# WS2811_Extender_V1_1.net
KiCad netlist of a schematic drawn in EAGLE
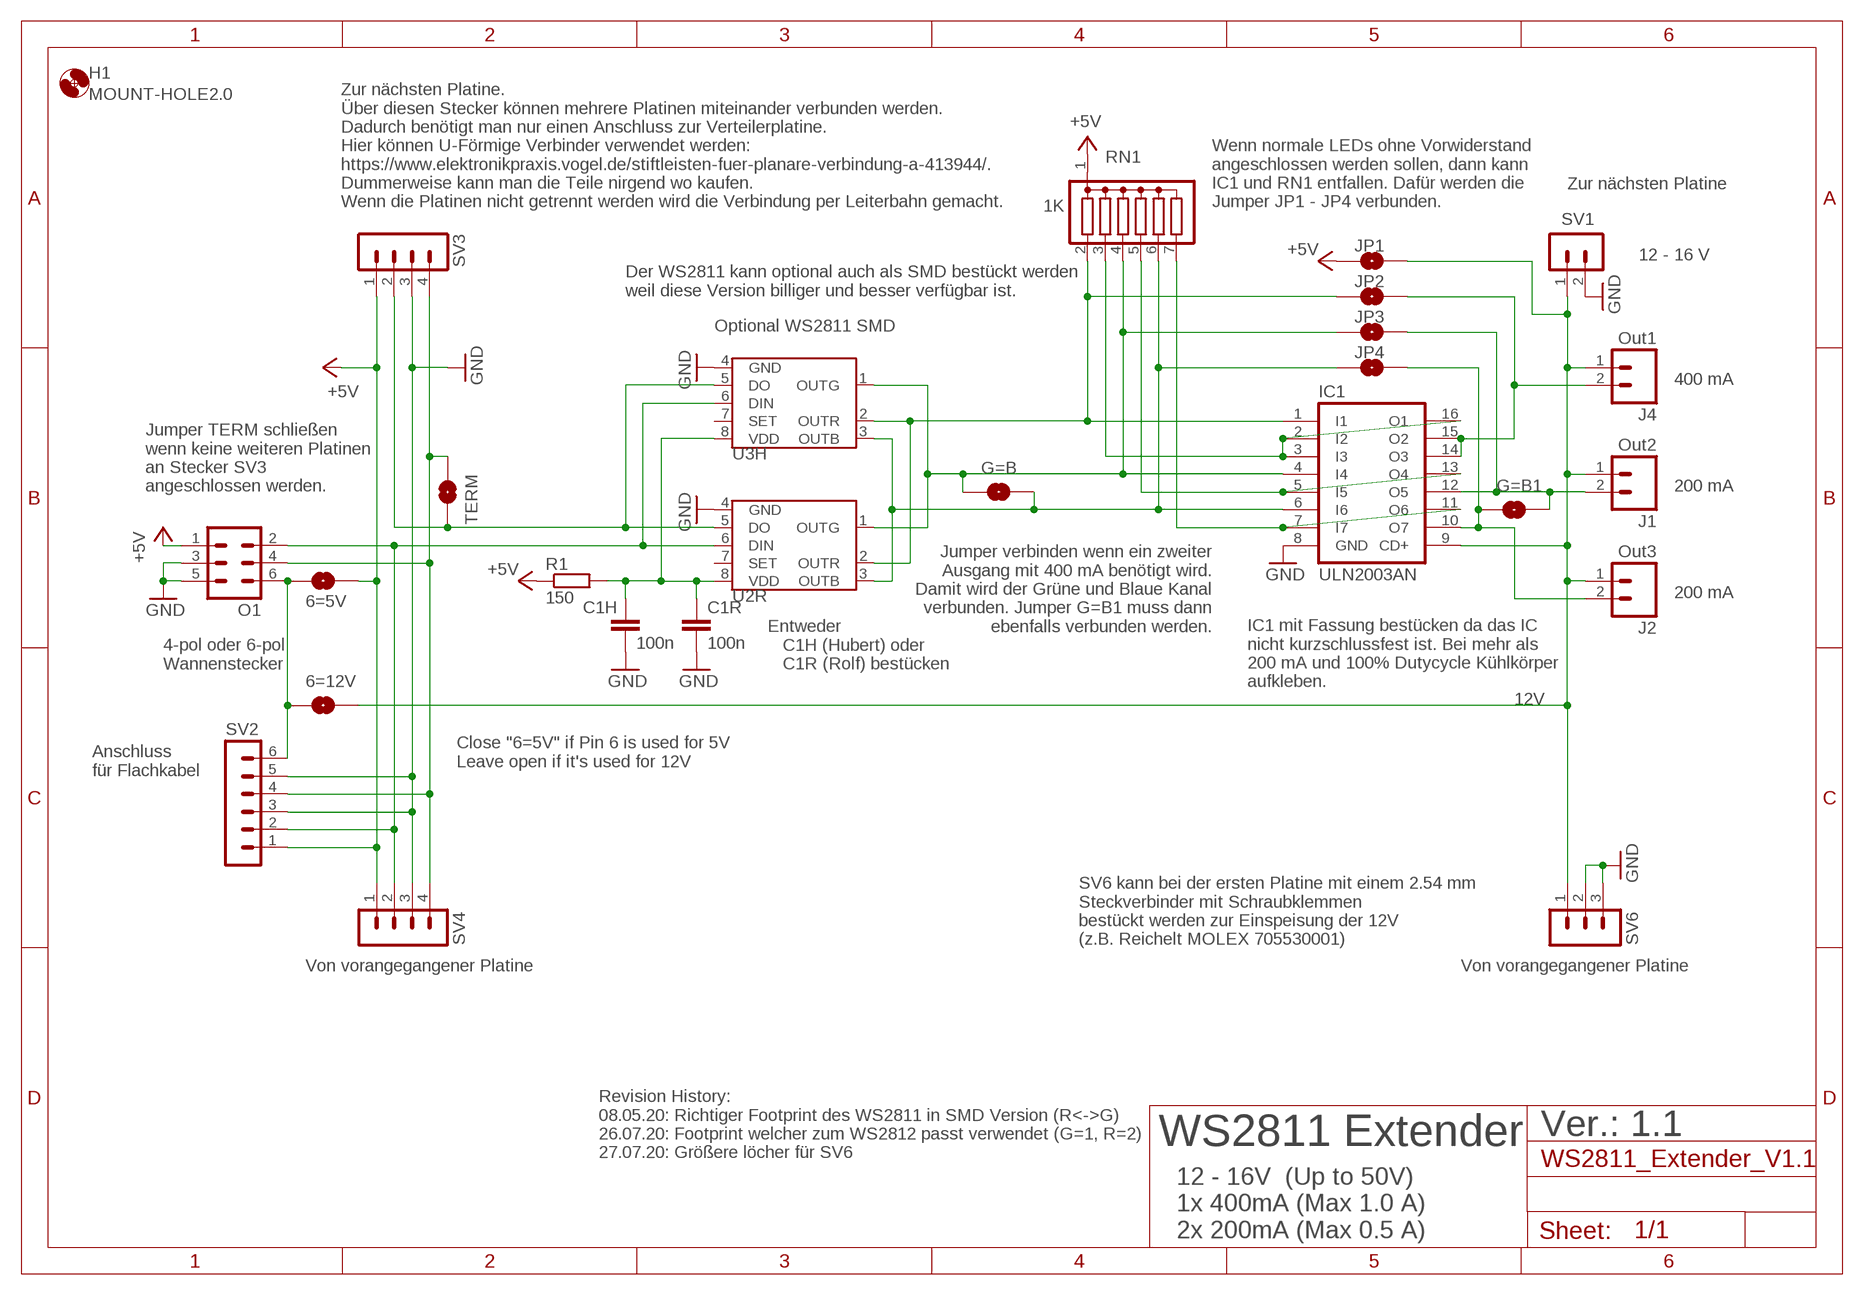
[diagram p0: schematic, sheet 1]

(export (version "E")
  (design (tool "Eeschema 10.0.6"))
  (components
    (comp (ref "6=5V")
      (value "SOLDERJUMPERNO")
      (footprint "eagle-import:SJ_2S-NO")
      (libsource (lib "eagle-import") (part "SOLDERJUMPERNO"))
    )
    (comp (ref "6=12V")
      (value "SOLDERJUMPERNO")
      (footprint "eagle-import:SJ_2S-NO")
      (libsource (lib "eagle-import") (part "SOLDERJUMPERNO"))
    )
    (comp (ref "C1H")
      (value "100n")
      (footprint "eagle-import:C1206")
      (libsource (lib "eagle-import") (part "C-EUC1206"))
    )
    (comp (ref "C1R")
      (value "100n")
      (footprint "eagle-import:C025-024X044")
      (libsource (lib "eagle-import") (part "C-EU025-024X044"))
    )
    (comp (ref "G=B")
      (value "SOLDERJUMPERNO")
      (footprint "eagle-import:SJ_2S-NO")
      (libsource (lib "eagle-import") (part "SOLDERJUMPERNO"))
    )
    (comp (ref "G=B1")
      (value "SOLDERJUMPERNO")
      (footprint "eagle-import:SJ_2S-NO")
      (libsource (lib "eagle-import") (part "SOLDERJUMPERNO"))
    )
    (comp (ref "H1")
      (value "MOUNT-HOLE2.0")
      (footprint "eagle-import:2,0")
      (libsource (lib "eagle-import") (part "MOUNT-HOLE2.0"))
    )
    (comp (ref "IC1")
      (value "ULN2003AN")
      (footprint "eagle-import:DIL16")
      (libsource (lib "eagle-import") (part "ULN2003AN"))
    )
    (comp (ref "J1")
      (value "Out2")
      (footprint "eagle-import:1X02")
      (libsource (lib "eagle-import") (part "M02PTH"))
    )
    (comp (ref "J2")
      (value "Out3")
      (footprint "eagle-import:1X02")
      (libsource (lib "eagle-import") (part "M02PTH"))
    )
    (comp (ref "J4")
      (value "Out1")
      (footprint "eagle-import:1X02")
      (libsource (lib "eagle-import") (part "M02PTH"))
    )
    (comp (ref "JP1")
      (value "SOLDERJUMPERNO")
      (footprint "eagle-import:SJ_2S-NO")
      (libsource (lib "eagle-import") (part "SOLDERJUMPERNO"))
    )
    (comp (ref "JP2")
      (value "SOLDERJUMPERNO")
      (footprint "eagle-import:SJ_2S-NO")
      (libsource (lib "eagle-import") (part "SOLDERJUMPERNO"))
    )
    (comp (ref "JP3")
      (value "SOLDERJUMPERNO")
      (footprint "eagle-import:SJ_2S-NO")
      (libsource (lib "eagle-import") (part "SOLDERJUMPERNO"))
    )
    (comp (ref "JP4")
      (value "SOLDERJUMPERNO")
      (footprint "eagle-import:SJ_2S-NO")
      (libsource (lib "eagle-import") (part "SOLDERJUMPERNO"))
    )
    (comp (ref "O1")
      (value "ML6")
      (footprint "eagle-import:ML6")
      (libsource (lib "eagle-import") (part "ML6"))
    )
    (comp (ref "R1")
      (value "150")
      (footprint "eagle-import:RCL_0207_2V")
      (libsource (lib "eagle-import") (part "RCL_R-EU_0207/2V"))
    )
    (comp (ref "RN1")
      (value "1K")
      (footprint "eagle-import:SIL7")
      (libsource (lib "eagle-import") (part "G06R"))
    )
    (comp (ref "SV1")
      (value "MA02-1")
      (footprint "eagle-import:MA02-1")
      (libsource (lib "eagle-import") (part "MA02-1"))
    )
    (comp (ref "SV2")
      (value "MA06-1")
      (footprint "eagle-import:MA06-1")
      (libsource (lib "eagle-import") (part "MA06-1"))
    )
    (comp (ref "SV3")
      (value "MA04-1")
      (footprint "eagle-import:MA04-1")
      (libsource (lib "eagle-import") (part "MA04-1"))
    )
    (comp (ref "SV4")
      (value "MA04-1")
      (footprint "eagle-import:MA04-1")
      (libsource (lib "eagle-import") (part "MA04-1"))
    )
    (comp (ref "SV6")
      (value "MA03-1")
      (footprint "eagle-import:MA03-1")
      (libsource (lib "eagle-import") (part "MA03-1"))
    )
    (comp (ref "TERM")
      (value "SOLDERJUMPERNO")
      (footprint "eagle-import:SJ_2S-NO")
      (libsource (lib "eagle-import") (part "SOLDERJUMPERNO"))
    )
    (comp (ref "U2R")
      (value "TINY45-20-DIP")
      (footprint "eagle-import:S3PO_MODUL_WS2811_SOUND_MP3-TF-16P_WS2811_AND_ATTINY_WS2811_DIP08")
      (libsource (lib "eagle-import") (part "S3PO_MODUL_WS2811_SOUND_MP3-TF-16P_WS2811_AND_ATTINY_WS2811-ICTINY45-20-DIP"))
    )
    (comp (ref "U3H")
      (value "WS2811 SOT-8")
      (footprint "eagle-import:SOP8")
      (libsource (lib "eagle-import") (part "S3PO_MODUL_WS2811_SOUND_MP3-TF-16P_WS2811_AND_ATTINY_WS2811-ICSOP8"))
    )
  )
  (nets
    (net (code "1") (name "+5V") (class "Default")
      (node (ref "6=5V") (pin "2") (pinfunction "2_2") (pintype "passive"))
      (node (ref "JP1") (pin "1") (pinfunction "1_1") (pintype "passive"))
      (node (ref "O1") (pin "1") (pinfunction "1_1") (pintype "passive"))
      (node (ref "R1") (pin "1") (pinfunction "1_1") (pintype "passive"))
      (node (ref "RN1") (pin "1") (pinfunction "1_1") (pintype "passive"))
      (node (ref "SV2") (pin "1") (pinfunction "1_1") (pintype "passive"))
      (node (ref "SV3") (pin "1") (pinfunction "1_1") (pintype "passive"))
      (node (ref "SV4") (pin "1") (pinfunction "1_1") (pintype "passive"))
    )
    (net (code "2") (name "/12V") (class "Default")
      (node (ref "6=12V") (pin "2") (pinfunction "2_2") (pintype "passive"))
      (node (ref "IC1") (pin "9") (pinfunction "CD+_9") (pintype "passive"))
      (node (ref "J1") (pin "1") (pinfunction "1_1") (pintype "passive"))
      (node (ref "J2") (pin "1") (pinfunction "1_1") (pintype "passive"))
      (node (ref "J4") (pin "1") (pinfunction "1_1") (pintype "passive"))
      (node (ref "JP1") (pin "2") (pinfunction "2_2") (pintype "passive"))
      (node (ref "SV1") (pin "1") (pinfunction "1_1") (pintype "passive"))
      (node (ref "SV6") (pin "1") (pinfunction "1_1") (pintype "passive"))
    )
    (net (code "3") (name "GND") (class "Default")
      (node (ref "C1H") (pin "2") (pinfunction "2_2") (pintype "passive"))
      (node (ref "C1R") (pin "2") (pinfunction "2_2") (pintype "passive"))
      (node (ref "IC1") (pin "8") (pinfunction "GND_8") (pintype "power_in"))
      (node (ref "O1") (pin "3") (pinfunction "3_3") (pintype "passive"))
      (node (ref "O1") (pin "5") (pinfunction "5_5") (pintype "passive"))
      (node (ref "SV1") (pin "2") (pinfunction "2_2") (pintype "passive"))
      (node (ref "SV2") (pin "3") (pinfunction "3_3") (pintype "passive"))
      (node (ref "SV2") (pin "5") (pinfunction "5_5") (pintype "passive"))
      (node (ref "SV3") (pin "3") (pinfunction "3_3") (pintype "passive"))
      (node (ref "SV4") (pin "3") (pinfunction "3_3") (pintype "passive"))
      (node (ref "SV6") (pin "2") (pinfunction "2_2") (pintype "passive"))
      (node (ref "SV6") (pin "3") (pinfunction "3_3") (pintype "passive"))
      (node (ref "U2R") (pin "4") (pinfunction "GND_4") (pintype "power_in"))
      (node (ref "U3H") (pin "4") (pinfunction "GND_4") (pintype "power_in"))
    )
    (net (code "4") (name "Net-(6=12V-Pad1)") (class "Default")
      (node (ref "6=12V") (pin "1") (pinfunction "1_1") (pintype "passive"))
      (node (ref "6=5V") (pin "1") (pinfunction "1_1") (pintype "passive"))
      (node (ref "O1") (pin "6") (pinfunction "6_6") (pintype "passive"))
      (node (ref "SV2") (pin "6") (pinfunction "6_6") (pintype "passive"))
    )
    (net (code "5") (name "Net-(IC1-I1)") (class "Default")
      (node (ref "IC1") (pin "1") (pinfunction "I1_1") (pintype "input"))
      (node (ref "JP2") (pin "1") (pinfunction "1_1") (pintype "passive"))
      (node (ref "RN1") (pin "2") (pinfunction "2_2") (pintype "passive"))
      (node (ref "U2R") (pin "2") (pinfunction "OUTR_2") (pintype "open_collector"))
      (node (ref "U3H") (pin "2") (pinfunction "OUTR_2") (pintype "open_collector"))
    )
    (net (code "6") (name "Net-(IC1-I2)") (class "Default")
      (node (ref "IC1") (pin "16") (pinfunction "O1_16") (pintype "open_collector"))
      (node (ref "IC1") (pin "2") (pinfunction "I2_2") (pintype "input"))
      (node (ref "IC1") (pin "3") (pinfunction "I3_3") (pintype "input"))
      (node (ref "RN1") (pin "3") (pinfunction "3_3") (pintype "passive"))
    )
    (net (code "7") (name "Net-(IC1-I4)") (class "Default")
      (node (ref "G=B") (pin "1") (pinfunction "1_1") (pintype "passive"))
      (node (ref "IC1") (pin "4") (pinfunction "I4_4") (pintype "input"))
      (node (ref "JP3") (pin "1") (pinfunction "1_1") (pintype "passive"))
      (node (ref "RN1") (pin "4") (pinfunction "4_4") (pintype "passive"))
      (node (ref "U2R") (pin "1") (pinfunction "OUTG_1") (pintype "open_collector"))
      (node (ref "U3H") (pin "1") (pinfunction "OUTG_1") (pintype "open_collector"))
    )
    (net (code "8") (name "Net-(IC1-I5)") (class "Default")
      (node (ref "IC1") (pin "13") (pinfunction "O4_13") (pintype "open_collector"))
      (node (ref "IC1") (pin "5") (pinfunction "I5_5") (pintype "input"))
      (node (ref "RN1") (pin "5") (pinfunction "5_5") (pintype "passive"))
    )
    (net (code "9") (name "Net-(IC1-I6)") (class "Default")
      (node (ref "G=B") (pin "2") (pinfunction "2_2") (pintype "passive"))
      (node (ref "IC1") (pin "6") (pinfunction "I6_6") (pintype "input"))
      (node (ref "JP4") (pin "1") (pinfunction "1_1") (pintype "passive"))
      (node (ref "RN1") (pin "6") (pinfunction "6_6") (pintype "passive"))
      (node (ref "U2R") (pin "3") (pinfunction "OUTB_3") (pintype "open_collector"))
      (node (ref "U3H") (pin "3") (pinfunction "OUTB_3") (pintype "open_collector"))
    )
    (net (code "10") (name "Net-(IC1-I7)") (class "Default")
      (node (ref "IC1") (pin "11") (pinfunction "O6_11") (pintype "open_collector"))
      (node (ref "IC1") (pin "7") (pinfunction "I7_7") (pintype "input"))
      (node (ref "RN1") (pin "7") (pinfunction "7_7") (pintype "passive"))
    )
    (net (code "11") (name "Net-(IC1-O2)") (class "Default")
      (node (ref "IC1") (pin "14") (pinfunction "O3_14") (pintype "open_collector"))
      (node (ref "IC1") (pin "15") (pinfunction "O2_15") (pintype "open_collector"))
      (node (ref "J4") (pin "2") (pinfunction "2_2") (pintype "passive"))
      (node (ref "JP2") (pin "2") (pinfunction "2_2") (pintype "passive"))
    )
    (net (code "12") (name "Net-(IC1-O5)") (class "Default")
      (node (ref "G=B1") (pin "2") (pinfunction "2_2") (pintype "passive"))
      (node (ref "IC1") (pin "12") (pinfunction "O5_12") (pintype "open_collector"))
      (node (ref "J1") (pin "2") (pinfunction "2_2") (pintype "passive"))
      (node (ref "JP3") (pin "2") (pinfunction "2_2") (pintype "passive"))
    )
    (net (code "13") (name "Net-(IC1-O7)") (class "Default")
      (node (ref "G=B1") (pin "1") (pinfunction "1_1") (pintype "passive"))
      (node (ref "IC1") (pin "10") (pinfunction "O7_10") (pintype "open_collector"))
      (node (ref "J2") (pin "2") (pinfunction "2_2") (pintype "passive"))
      (node (ref "JP4") (pin "2") (pinfunction "2_2") (pintype "passive"))
    )
    (net (code "14") (name "Net-(O1-Pad4)") (class "Default")
      (node (ref "O1") (pin "4") (pinfunction "4_4") (pintype "passive"))
      (node (ref "SV2") (pin "4") (pinfunction "4_4") (pintype "passive"))
      (node (ref "SV3") (pin "4") (pinfunction "4_4") (pintype "passive"))
      (node (ref "SV4") (pin "4") (pinfunction "4_4") (pintype "passive"))
      (node (ref "TERM") (pin "1") (pinfunction "1_1") (pintype "passive"))
    )
    (net (code "15") (name "Net-(U2R-DIN)") (class "Default")
      (node (ref "O1") (pin "2") (pinfunction "2_2") (pintype "passive"))
      (node (ref "SV2") (pin "2") (pinfunction "2_2") (pintype "passive"))
      (node (ref "SV4") (pin "2") (pinfunction "2_2") (pintype "passive"))
      (node (ref "U2R") (pin "6") (pinfunction "DIN_6") (pintype "input"))
      (node (ref "U3H") (pin "6") (pinfunction "DIN_6") (pintype "input"))
    )
    (net (code "16") (name "Net-(U2R-DO)") (class "Default")
      (node (ref "SV3") (pin "2") (pinfunction "2_2") (pintype "passive"))
      (node (ref "TERM") (pin "2") (pinfunction "2_2") (pintype "passive"))
      (node (ref "U2R") (pin "5") (pinfunction "DO_5") (pintype "output"))
      (node (ref "U3H") (pin "5") (pinfunction "DO_5") (pintype "output"))
    )
    (net (code "17") (name "Net-(U2R-VDD)") (class "Default")
      (node (ref "C1H") (pin "1") (pinfunction "1_1") (pintype "passive"))
      (node (ref "C1R") (pin "1") (pinfunction "1_1") (pintype "passive"))
      (node (ref "R1") (pin "2") (pinfunction "2_2") (pintype "passive"))
      (node (ref "U2R") (pin "8") (pinfunction "VDD_8") (pintype "power_in"))
      (node (ref "U3H") (pin "8") (pinfunction "VDD_8") (pintype "power_in"))
    )
    (net (code "18") (name "unconnected-(U2R-SET-Pad7)") (class "Default")
      (node (ref "U2R") (pin "7") (pinfunction "SET_7") (pintype "bidirectional"))
    )
    (net (code "19") (name "unconnected-(U3H-SET-Pad7)") (class "Default")
      (node (ref "U3H") (pin "7") (pinfunction "SET_7") (pintype "bidirectional"))
    )
  )
)
